# Power_Regulation_and_Protection.net
KiCad netlist of a schematic drawn in Altium Designer
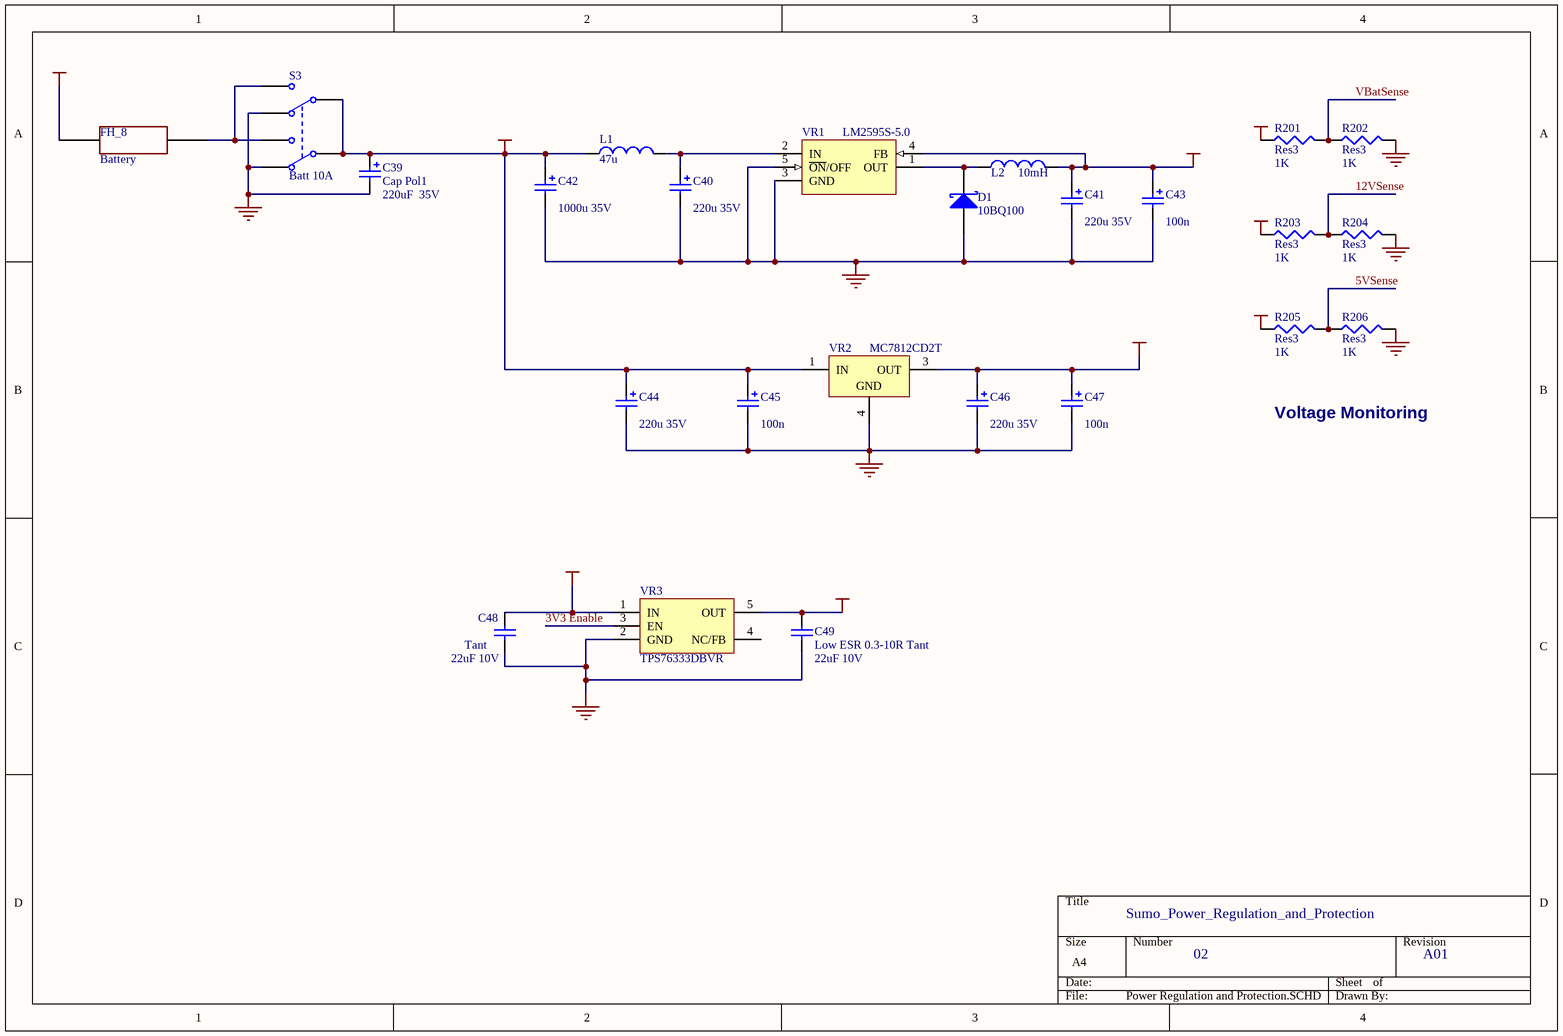
[diagram p0: Power Regulation and Protection.SCHDOC]

(export (version "E")
  (design (tool "Eeschema 10.0.6"))
  (components
    (comp (ref "C39")
      (value "Cap Pol1")
      (footprint "CAPPOL5-10X13")
      (description "Polarized Capacitor (Radial)")
      (fields (field (name "ALTIUM_VALUE") "220uF  35V") (field (name "PUBLISHER") "Altium Limited"))
      (libsource (lib "Miscellaneous Devices") (part "Cap Pol1"))
    )
    (comp (ref "C40")
      (value "220u 35V")
      (footprint "CAPPOL5-10X13")
      (description "Polarized Capacitor (Radial)")
      (fields (field (name "Comment") "Cap Pol1") (field (name "PUBLISHER") "Altium Limited"))
      (libsource (lib "Miscellaneous Devices") (part "Cap Pol1"))
    )
    (comp (ref "C41")
      (value "220u 35V")
      (footprint "CAPPOL5-10X13")
      (description "Polarized Capacitor (Radial)")
      (fields (field (name "Comment") "Cap Pol1") (field (name "PUBLISHER") "Altium Limited"))
      (libsource (lib "Miscellaneous Devices") (part "Cap Pol1"))
    )
    (comp (ref "C42")
      (value "1000u 35V")
      (footprint "CAPPOL7.5-16")
      (description "Polarized Capacitor (Radial)")
      (fields (field (name "Comment") "Cap Pol1") (field (name "PUBLISHER") "Altium Limited"))
      (libsource (lib "Miscellaneous Devices") (part "Cap Pol1"))
    )
    (comp (ref "C43")
      (value "100n")
      (footprint "CC2012-0805")
      (description "Polarized Capacitor (Surface Mount)")
      (fields (field (name "Comment") "Cap Pol3") (field (name "PUBLISHER") "Altium Limited"))
      (libsource (lib "Miscellaneous Devices") (part "Cap Pol3"))
    )
    (comp (ref "C44")
      (value "220u 35V")
      (footprint "CAPPOL5-10X13")
      (description "Polarized Capacitor (Radial)")
      (fields (field (name "Comment") "Cap Pol1") (field (name "PUBLISHER") "Altium Limited"))
      (libsource (lib "Miscellaneous Devices") (part "Cap Pol1"))
    )
    (comp (ref "C45")
      (value "100n")
      (footprint "CC2012-0805")
      (description "Polarized Capacitor (Surface Mount)")
      (fields (field (name "Comment") "Cap Pol3") (field (name "PUBLISHER") "Altium Limited"))
      (libsource (lib "Miscellaneous Devices") (part "Cap Pol3"))
    )
    (comp (ref "C46")
      (value "220u 35V")
      (footprint "CAPPOL5-10X13")
      (description "Polarized Capacitor (Radial)")
      (fields (field (name "Comment") "Cap Pol1") (field (name "PUBLISHER") "Altium Limited"))
      (libsource (lib "Miscellaneous Devices") (part "Cap Pol1"))
    )
    (comp (ref "C47")
      (value "100n")
      (footprint "CC2012-0805")
      (description "Polarized Capacitor (Surface Mount)")
      (fields (field (name "Comment") "Cap Pol3") (field (name "PUBLISHER") "Altium Limited"))
      (libsource (lib "Miscellaneous Devices") (part "Cap Pol3"))
    )
    (comp (ref "C48")
      (value "Tant")
      (footprint "CC4532-1812")
      (description "Capacitor (Semiconductor SIM Model)")
      (fields (field (name "ALTIUM_VALUE") "22uF 10V") (field (name "PUBLISHER") "Altium Limited"))
      (libsource (lib "Miscellaneous Devices") (part "Cap Semi"))
    )
    (comp (ref "C49")
      (value "Low ESR 0.3-10R Tant")
      (footprint "CC4532-1812")
      (description "Capacitor (Semiconductor SIM Model)")
      (fields (field (name "ALTIUM_VALUE") "22uF 10V") (field (name "PUBLISHER") "Altium Limited"))
      (libsource (lib "Miscellaneous Devices") (part "Cap Semi"))
    )
    (comp (ref "D1")
      (value "10BQ100")
      (footprint "SMB")
      (description "Schottky Rectifier")
      (fields (field (name "PUBLISHER") "Altium Limited"))
      (libsource (lib "IR Discrete Diode") (part "10BQ100"))
    )
    (comp (ref "FH_8")
      (value "Battery")
      (footprint "FuseHolder Miniblade")
      (description "Fuse Holder")
      (libsource (lib "Sumo") (part "Fuse_Holder"))
    )
    (comp (ref "L1")
      (value "47u")
      (footprint "CDRH125 Inductor")
      (description "Inductor")
      (fields (field (name "PUBLISHER") "Altium Limited"))
      (libsource (lib "Miscellaneous Devices") (part "Inductor"))
    )
    (comp (ref "L2")
      (value "10mH")
      (footprint "CDRH125 Inductor")
      (description "Inductor")
      (fields (field (name "PUBLISHER") "Altium Limited"))
      (libsource (lib "Miscellaneous Devices") (part "Inductor"))
    )
    (comp (ref "R201")
      (value "Res3")
      (footprint "R2012-0805")
      (description "Resistor")
      (fields (field (name "ALTIUM_VALUE") "1K") (field (name "PUBLISHER") "Altium Limited"))
      (libsource (lib "Miscellaneous Devices") (part "Res3"))
    )
    (comp (ref "R202")
      (value "Res3")
      (footprint "R2012-0805")
      (description "Resistor")
      (fields (field (name "ALTIUM_VALUE") "1K") (field (name "PUBLISHER") "Altium Limited"))
      (libsource (lib "Miscellaneous Devices") (part "Res3"))
    )
    (comp (ref "R203")
      (value "Res3")
      (footprint "R2012-0805")
      (description "Resistor")
      (fields (field (name "ALTIUM_VALUE") "1K") (field (name "PUBLISHER") "Altium Limited"))
      (libsource (lib "Miscellaneous Devices") (part "Res3"))
    )
    (comp (ref "R204")
      (value "Res3")
      (footprint "R2012-0805")
      (description "Resistor")
      (fields (field (name "ALTIUM_VALUE") "1K") (field (name "PUBLISHER") "Altium Limited"))
      (libsource (lib "Miscellaneous Devices") (part "Res3"))
    )
    (comp (ref "R205")
      (value "Res3")
      (footprint "R2012-0805")
      (description "Resistor")
      (fields (field (name "ALTIUM_VALUE") "1K") (field (name "PUBLISHER") "Altium Limited"))
      (libsource (lib "Miscellaneous Devices") (part "Res3"))
    )
    (comp (ref "R206")
      (value "Res3")
      (footprint "R2012-0805")
      (description "Resistor")
      (fields (field (name "ALTIUM_VALUE") "1K") (field (name "PUBLISHER") "Altium Limited"))
      (libsource (lib "Miscellaneous Devices") (part "Res3"))
    )
    (comp (ref "S3")
      (value "Batt 10A")
      (footprint "SW  DPDT")
      (description "Switch")
      (fields (field (name "PUBLISHER") "Altium Limited"))
      (libsource (lib "Sumo") (part "SW DPDT"))
    )
    (comp (ref "VR1")
      (value "LM2595S-5.0")
      (footprint "TO-263 5 Pin SMT")
      (description "Simple Switcher Power Converter 150 kHz 1A Step Down Voltage Regulator")
      (fields (field (name "PUBLISHER") "Altium Limited"))
      (libsource (lib "NSC Power Mgt Switching Regulator") (part "LM2595S-5.0"))
    )
    (comp (ref "VR2")
      (value "MC7812CD2T")
      (footprint "936-03")
      (description "Three-Terminal Positive Voltage Regulator")
      (fields (field (name "PUBLISHER") "Altium Limited"))
      (libsource (lib "ON Semi Power Mgt Voltage Regulator") (part "MC7812CD2T"))
    )
    (comp (ref "VR3")
      (value "TPS76333DBVR")
      (footprint "SOT-23-5")
      (libsource (lib "TTCustomLibrary") (part "TPS76333DBVR"))
    )
  )
  (nets
    (net (code "1") (name "/3V3 Enable") (class "Default")
      (node (ref "VR3") (pin "3") (pinfunction "EN_3") (pintype "passive"))
    )
    (net (code "2") (name "/5VSense") (class "Default")
      (node (ref "R205") (pin "2") (pinfunction "2_2") (pintype "passive"))
      (node (ref "R206") (pin "1") (pinfunction "1_1") (pintype "passive"))
    )
    (net (code "3") (name "/12VSense") (class "Default")
      (node (ref "R203") (pin "2") (pinfunction "2_2") (pintype "passive"))
      (node (ref "R204") (pin "1") (pinfunction "1_1") (pintype "passive"))
    )
    (net (code "4") (name "/VBatSense") (class "Default")
      (node (ref "R201") (pin "2") (pinfunction "2_2") (pintype "passive"))
      (node (ref "R202") (pin "1") (pinfunction "1_1") (pintype "passive"))
    )
    (net (code "5") (name "3V3") (class "Default")
      (node (ref "C49") (pin "2") (pinfunction "2_2") (pintype "passive"))
      (node (ref "VR3") (pin "5") (pinfunction "OUT_5") (pintype "passive"))
    )
    (net (code "6") (name "5V") (class "Default")
      (node (ref "C41") (pin "1") (pinfunction "1_1") (pintype "passive"))
      (node (ref "C43") (pin "1") (pinfunction "1_1") (pintype "passive"))
      (node (ref "C48") (pin "2") (pinfunction "2_2") (pintype "passive"))
      (node (ref "L2") (pin "2") (pinfunction "2_2") (pintype "passive"))
      (node (ref "R205") (pin "1") (pinfunction "1_1") (pintype "passive"))
      (node (ref "VR1") (pin "4") (pinfunction "FB_4") (pintype "input"))
      (node (ref "VR3") (pin "1") (pinfunction "IN_1") (pintype "passive"))
    )
    (net (code "7") (name "12V") (class "Default")
      (node (ref "C46") (pin "1") (pinfunction "1_1") (pintype "passive"))
      (node (ref "C47") (pin "1") (pinfunction "1_1") (pintype "passive"))
      (node (ref "R203") (pin "1") (pinfunction "1_1") (pintype "passive"))
      (node (ref "VR2") (pin "3") (pinfunction "OUT_3") (pintype "power_in"))
    )
    (net (code "8") (name "GND") (class "Default")
      (node (ref "C39") (pin "2") (pinfunction "2_2") (pintype "passive"))
      (node (ref "C40") (pin "2") (pinfunction "2_2") (pintype "passive"))
      (node (ref "C41") (pin "2") (pinfunction "2_2") (pintype "passive"))
      (node (ref "C42") (pin "2") (pinfunction "2_2") (pintype "passive"))
      (node (ref "C43") (pin "2") (pinfunction "2_2") (pintype "passive"))
      (node (ref "C44") (pin "2") (pinfunction "2_2") (pintype "passive"))
      (node (ref "C45") (pin "2") (pinfunction "2_2") (pintype "passive"))
      (node (ref "C46") (pin "2") (pinfunction "2_2") (pintype "passive"))
      (node (ref "C47") (pin "2") (pinfunction "2_2") (pintype "passive"))
      (node (ref "C48") (pin "1") (pinfunction "1_1") (pintype "passive"))
      (node (ref "C49") (pin "1") (pinfunction "1_1") (pintype "passive"))
      (node (ref "D1") (pin "1") (pinfunction "A_1") (pintype "passive"))
      (node (ref "R202") (pin "2") (pinfunction "2_2") (pintype "passive"))
      (node (ref "R204") (pin "2") (pinfunction "2_2") (pintype "passive"))
      (node (ref "R206") (pin "2") (pinfunction "2_2") (pintype "passive"))
      (node (ref "S3") (pin "1") (pinfunction "NC1_1") (pintype "passive"))
      (node (ref "S3") (pin "4") (pinfunction "NC2_4") (pintype "passive"))
      (node (ref "VR1") (pin "3") (pinfunction "GND_3") (pintype "power_in"))
      (node (ref "VR1") (pin "5") (pinfunction "~{ON}/OFF_5") (pintype "input"))
      (node (ref "VR2") (pin "4") (pinfunction "GND_4") (pintype "power_in"))
      (node (ref "VR3") (pin "2") (pinfunction "GND_2") (pintype "passive"))
    )
    (net (code "9") (name "Net-(D1-K)") (class "Default")
      (node (ref "D1") (pin "2") (pinfunction "K_2") (pintype "passive"))
      (node (ref "L2") (pin "1") (pinfunction "1_1") (pintype "passive"))
      (node (ref "VR1") (pin "1") (pinfunction "OUT_1") (pintype "power_in"))
    )
    (net (code "10") (name "Net-(S3-NO1)") (class "Default")
      (node (ref "FH_8") (pin "2") (pinfunction "2_2") (pintype "passive"))
      (node (ref "S3") (pin "3") (pinfunction "NO1_3") (pintype "passive"))
      (node (ref "S3") (pin "6") (pinfunction "NO2_6") (pintype "passive"))
    )
    (net (code "11") (name "Net-(VR1-IN)") (class "Default")
      (node (ref "C40") (pin "1") (pinfunction "1_1") (pintype "passive"))
      (node (ref "L1") (pin "2") (pinfunction "2_2") (pintype "passive"))
      (node (ref "VR1") (pin "2") (pinfunction "IN_2") (pintype "power_in"))
    )
    (net (code "12") (name "VBat") (class "Default")
      (node (ref "C39") (pin "1") (pinfunction "1_1") (pintype "passive"))
      (node (ref "C42") (pin "1") (pinfunction "1_1") (pintype "passive"))
      (node (ref "C44") (pin "1") (pinfunction "1_1") (pintype "passive"))
      (node (ref "C45") (pin "1") (pinfunction "1_1") (pintype "passive"))
      (node (ref "L1") (pin "1") (pinfunction "1_1") (pintype "passive"))
      (node (ref "R201") (pin "1") (pinfunction "1_1") (pintype "passive"))
      (node (ref "S3") (pin "2") (pinfunction "COMMON1_2") (pintype "passive"))
      (node (ref "S3") (pin "5") (pinfunction "COMMON2_5") (pintype "passive"))
      (node (ref "VR2") (pin "1") (pinfunction "IN_1") (pintype "power_in"))
    )
    (net (code "13") (name "VBatIn") (class "Default")
      (node (ref "FH_8") (pin "1") (pinfunction "1_1") (pintype "passive"))
    )
    (net (code "14") (name "unconnected-(VR3-NC{slash}FB-Pad4)") (class "Default")
      (node (ref "VR3") (pin "4") (pinfunction "NC/FB_4") (pintype "passive"))
    )
  )
)
